# Modem.net
KiCad netlist of a schematic drawn in Altium Designer
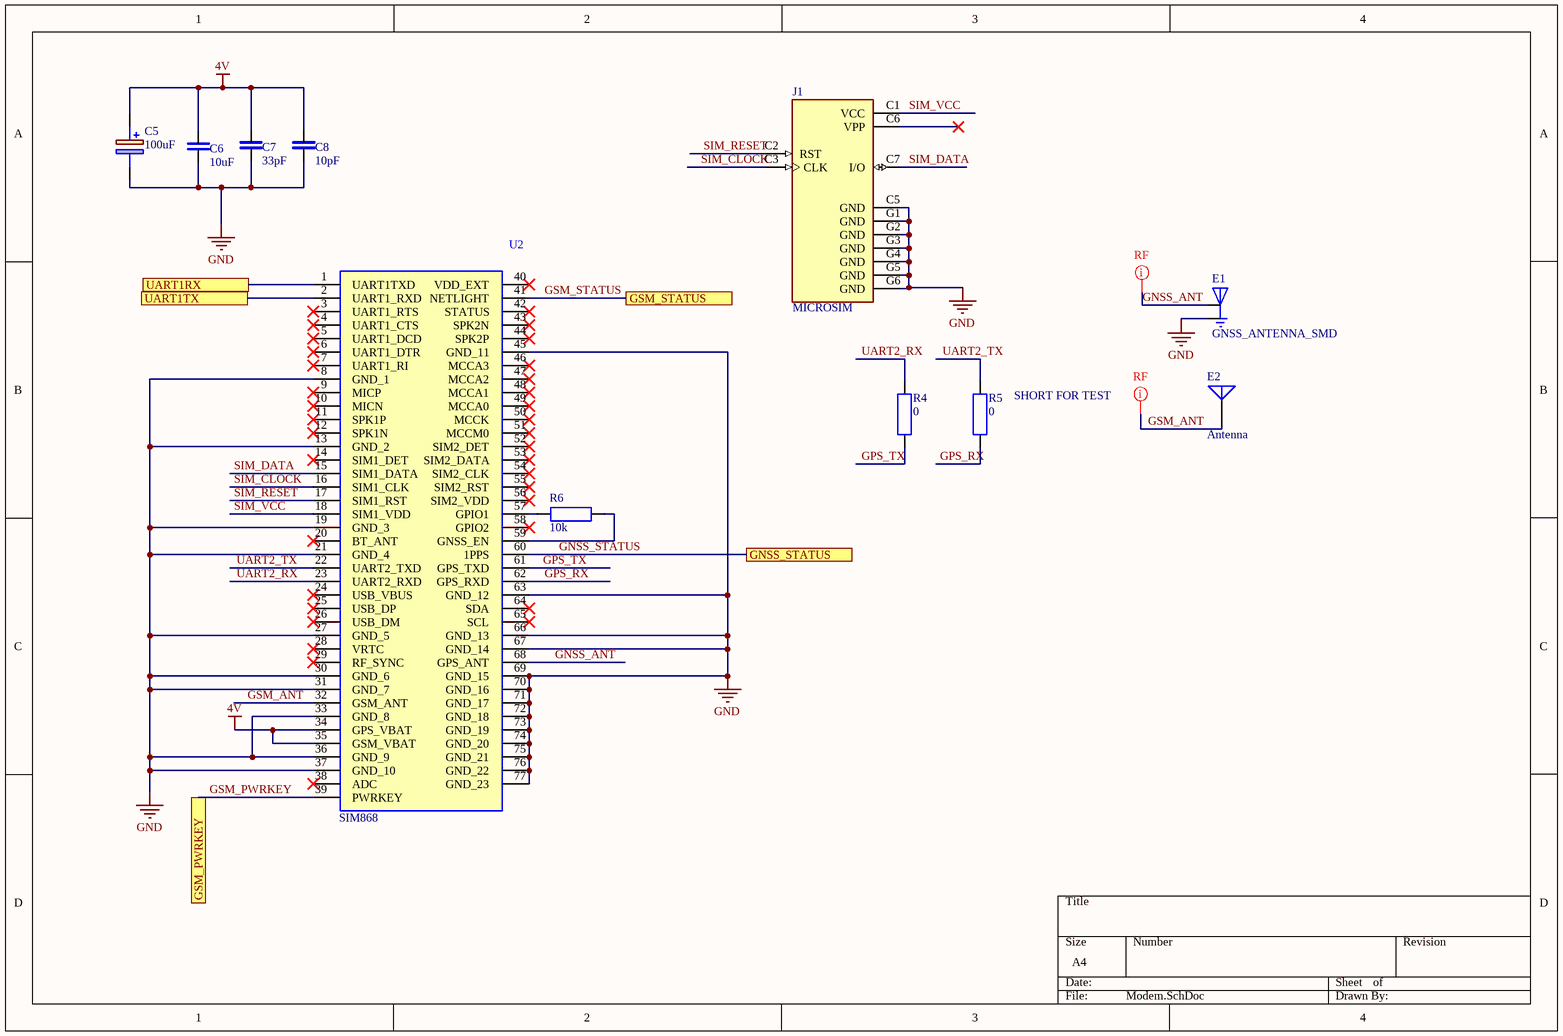
[diagram p0: Modem.SchDoc]

(export (version "E")
  (design (tool "Eeschema 10.0.6"))
  (components
    (comp (ref "C5")
      (value "100uF")
      (footprint "TANTALUM_CAP_0805")
      (description "T491C107K016AT")
      (fields (field (name "MOUSER PART NUMBER") "80-T491C107K016AT"))
      (libsource (lib "Passive_Components") (part "SMT_TANTALUM_CAP"))
    )
    (comp (ref "C6")
      (value "10uF")
      (footprint "CAP_0805")
      (fields (field (name "MP") "LD051A270KAB2A"))
      (libsource (lib "Passive_Components") (part "SMT_CAP"))
    )
    (comp (ref "C7")
      (value "33pF")
      (footprint "CAP_0805")
      (fields (field (name "MP") "LD051A270KAB2A"))
      (libsource (lib "Passive_Components") (part "SMT_CAP"))
    )
    (comp (ref "C8")
      (value "10pF")
      (footprint "CAP_0805")
      (fields (field (name "MP") "LD051A270KAB2A"))
      (libsource (lib "Passive_Components") (part "SMT_CAP"))
    )
    (comp (ref "E1")
      (value "GNSS_ANTENNA_SMD")
      (footprint "GNSS_ANTENNA_SMD")
      (description "Ceramic GNSS antenna 25*25 SMD")
      (fields (field (name "MF") "Linx") (field (name "MP") "ANT-GNSSCP-TH18L1"))
      (libsource (lib "Extras") (part "GNSS_ANTENNA_SMD"))
    )
    (comp (ref "E2")
      (value "Antenna")
      (footprint "PIN1")
      (description "Generic Antenna")
      (fields (field (name "PUBLISHER") "Altium Limited"))
      (libsource (lib "Miscellaneous Devices") (part "Antenna"))
    )
    (comp (ref "J1")
      (value "MICROSIM")
      (footprint "MICROSIM")
      (description "PART NR: 78646-3001")
      (fields (field (name "MP") "78646-3001") (field (name "MF") "Molex"))
      (libsource (lib "Extras") (part "MICROSIM"))
    )
    (comp (ref "R4")
      (value "0")
      (footprint "RES_0805")
      (fields
        (field (name "MP") "2-2176053-0")
        (field (name "TOLERANCE") "1%")
        (field (name "MF") "TE Connectivity")
      )
      (libsource (lib "Passive_Components") (part "SMT_RES"))
    )
    (comp (ref "R5")
      (value "0")
      (footprint "RES_0805")
      (fields
        (field (name "MP") "2-2176053-0")
        (field (name "TOLERANCE") "1%")
        (field (name "MF") "TE Connectivity")
      )
      (libsource (lib "Passive_Components") (part "SMT_RES"))
    )
    (comp (ref "R6")
      (value "10k")
      (footprint "RES_0805")
      (fields
        (field (name "MP") "2-2176053-0")
        (field (name "TOLERANCE") "1%")
        (field (name "MF") "TE Connectivity")
      )
      (libsource (lib "Passive_Components") (part "SMT_RES"))
    )
    (comp (ref "U2")
      (value "GPRS,GSM,GNSS Modem")
      (footprint "SIM868")
      (fields (field (name "MANUFACTURER_PART_NUMBER") "SIM868") (field (name "SYMBOLNAME_1") "SIM868"))
      (libsource (lib "IC") (part "SIM868"))
    )
  )
  (nets
    (net (code "1") (name "/GNSS_ANT") (class "Default")
      (node (ref "E1") (pin "1") (pinfunction "FEEDING_1") (pintype "passive"))
      (node (ref "U2") (pin "68") (pinfunction "GPS_ANT_68") (pintype "power_in"))
    )
    (net (code "2") (name "/GNSS_STATUS") (class "Default")
      (node (ref "U2") (pin "60") (pinfunction "1PPS_60") (pintype "power_in"))
    )
    (net (code "3") (name "/GPS_RX") (class "Default")
      (node (ref "R5") (pin "1") (pinfunction "1_1") (pintype "passive"))
      (node (ref "U2") (pin "62") (pinfunction "GPS_RXD_62") (pintype "power_in"))
    )
    (net (code "4") (name "/GPS_TX") (class "Default")
      (node (ref "R4") (pin "1") (pinfunction "1_1") (pintype "passive"))
      (node (ref "U2") (pin "61") (pinfunction "GPS_TXD_61") (pintype "power_in"))
    )
    (net (code "5") (name "/GSM_ANT") (class "Default")
      (node (ref "E2") (pin "1") (pinfunction "A_1") (pintype "passive"))
      (node (ref "U2") (pin "32") (pinfunction "GSM_ANT_32") (pintype "power_in"))
    )
    (net (code "6") (name "/GSM_PWRKEY") (class "Default")
      (node (ref "U2") (pin "39") (pinfunction "PWRKEY_39") (pintype "power_in"))
    )
    (net (code "7") (name "/GSM_STATUS") (class "Default")
      (node (ref "U2") (pin "41") (pinfunction "NETLIGHT_41") (pintype "power_in"))
    )
    (net (code "8") (name "/SIM_CLOCK") (class "Default")
      (node (ref "J1") (pin "C3") (pinfunction "CLK_C3") (pintype "input"))
      (node (ref "U2") (pin "16") (pinfunction "SIM1_CLK_16") (pintype "power_in"))
    )
    (net (code "9") (name "/SIM_DATA") (class "Default")
      (node (ref "J1") (pin "C7") (pinfunction "I/O_C7") (pintype "bidirectional"))
      (node (ref "U2") (pin "15") (pinfunction "SIM1_DATA_15") (pintype "power_in"))
    )
    (net (code "10") (name "/SIM_RESET") (class "Default")
      (node (ref "J1") (pin "C2") (pinfunction "RST_C2") (pintype "input"))
      (node (ref "U2") (pin "17") (pinfunction "SIM1_RST_17") (pintype "power_in"))
    )
    (net (code "11") (name "/SIM_VCC") (class "Default")
      (node (ref "J1") (pin "C1") (pinfunction "VCC_C1") (pintype "power_in"))
      (node (ref "U2") (pin "18") (pinfunction "SIM1_VDD_18") (pintype "power_in"))
    )
    (net (code "12") (name "/UART1RX") (class "Default")
      (node (ref "U2") (pin "1") (pinfunction "UART1TXD_1") (pintype "power_in"))
    )
    (net (code "13") (name "/UART1TX") (class "Default")
      (node (ref "U2") (pin "2") (pinfunction "UART1_RXD_2") (pintype "power_in"))
    )
    (net (code "14") (name "/UART2_RX") (class "Default")
      (node (ref "R4") (pin "2") (pinfunction "2_2") (pintype "passive"))
      (node (ref "U2") (pin "23") (pinfunction "UART2_RXD_23") (pintype "power_in"))
    )
    (net (code "15") (name "/UART2_TX") (class "Default")
      (node (ref "R5") (pin "2") (pinfunction "2_2") (pintype "passive"))
      (node (ref "U2") (pin "22") (pinfunction "UART2_TXD_22") (pintype "power_in"))
    )
    (net (code "16") (name "4V") (class "Default")
      (node (ref "C5") (pin "1") (pinfunction "+_1") (pintype "passive"))
      (node (ref "C6") (pin "2") (pinfunction "2_2") (pintype "passive"))
      (node (ref "C7") (pin "2") (pinfunction "2_2") (pintype "passive"))
      (node (ref "C8") (pin "2") (pinfunction "2_2") (pintype "passive"))
      (node (ref "U2") (pin "34") (pinfunction "GPS_VBAT_34") (pintype "power_in"))
      (node (ref "U2") (pin "35") (pinfunction "GSM_VBAT_35") (pintype "power_in"))
    )
    (net (code "17") (name "GND") (class "Default")
      (node (ref "C5") (pin "2") (pinfunction "-_2") (pintype "passive"))
      (node (ref "C6") (pin "1") (pinfunction "1_1") (pintype "passive"))
      (node (ref "C7") (pin "1") (pinfunction "1_1") (pintype "passive"))
      (node (ref "C8") (pin "1") (pinfunction "1_1") (pintype "passive"))
      (node (ref "E1") (pin "2") (pinfunction "GND_2") (pintype "power_in"))
      (node (ref "J1") (pin "C5") (pinfunction "GND_C5") (pintype "power_in"))
      (node (ref "J1") (pin "G1") (pinfunction "GND_G1") (pintype "power_in"))
      (node (ref "J1") (pin "G2") (pinfunction "GND_G2") (pintype "power_in"))
      (node (ref "J1") (pin "G3") (pinfunction "GND_G3") (pintype "power_in"))
      (node (ref "J1") (pin "G4") (pinfunction "GND_G4") (pintype "power_in"))
      (node (ref "J1") (pin "G5") (pinfunction "GND_G5") (pintype "power_in"))
      (node (ref "J1") (pin "G6") (pinfunction "GND_G6") (pintype "power_in"))
      (node (ref "U2") (pin "13") (pinfunction "GND_2_13") (pintype "power_in"))
      (node (ref "U2") (pin "19") (pinfunction "GND_3_19") (pintype "power_in"))
      (node (ref "U2") (pin "21") (pinfunction "GND_4_21") (pintype "power_in"))
      (node (ref "U2") (pin "27") (pinfunction "GND_5_27") (pintype "power_in"))
      (node (ref "U2") (pin "30") (pinfunction "GND_6_30") (pintype "power_in"))
      (node (ref "U2") (pin "31") (pinfunction "GND_7_31") (pintype "power_in"))
      (node (ref "U2") (pin "33") (pinfunction "GND_8_33") (pintype "power_in"))
      (node (ref "U2") (pin "36") (pinfunction "GND_9_36") (pintype "power_in"))
      (node (ref "U2") (pin "37") (pinfunction "GND_10_37") (pintype "power_in"))
      (node (ref "U2") (pin "45") (pinfunction "GND_11_45") (pintype "power_in"))
      (node (ref "U2") (pin "63") (pinfunction "GND_12_63") (pintype "power_in"))
      (node (ref "U2") (pin "66") (pinfunction "GND_13_66") (pintype "power_in"))
      (node (ref "U2") (pin "67") (pinfunction "GND_14_67") (pintype "power_in"))
      (node (ref "U2") (pin "69") (pinfunction "GND_15_69") (pintype "power_in"))
      (node (ref "U2") (pin "70") (pinfunction "GND_16_70") (pintype "power_in"))
      (node (ref "U2") (pin "71") (pinfunction "GND_17_71") (pintype "power_in"))
      (node (ref "U2") (pin "72") (pinfunction "GND_18_72") (pintype "power_in"))
      (node (ref "U2") (pin "73") (pinfunction "GND_19_73") (pintype "power_in"))
      (node (ref "U2") (pin "74") (pinfunction "GND_20_74") (pintype "power_in"))
      (node (ref "U2") (pin "75") (pinfunction "GND_21_75") (pintype "power_in"))
      (node (ref "U2") (pin "76") (pinfunction "GND_22_76") (pintype "power_in"))
      (node (ref "U2") (pin "77") (pinfunction "GND_23_77") (pintype "power_in"))
      (node (ref "U2") (pin "8") (pinfunction "GND_1_8") (pintype "power_in"))
    )
    (net (code "18") (name "Net-(U2-GNSS_EN)") (class "Default")
      (node (ref "R6") (pin "2") (pinfunction "2_2") (pintype "passive"))
      (node (ref "U2") (pin "59") (pinfunction "GNSS_EN_59") (pintype "power_in"))
    )
    (net (code "19") (name "Net-(U2-GPIO1)") (class "Default")
      (node (ref "R6") (pin "1") (pinfunction "1_1") (pintype "passive"))
      (node (ref "U2") (pin "57") (pinfunction "GPIO1_57") (pintype "power_in"))
    )
    (net (code "20") (name "unconnected-(J1-VPP-PadC6)") (class "Default")
      (node (ref "J1") (pin "C6") (pinfunction "VPP_C6") (pintype "power_in+no_connect"))
    )
    (net (code "21") (name "unconnected-(U2-ADC-Pad38)") (class "Default")
      (node (ref "U2") (pin "38") (pinfunction "ADC_38") (pintype "power_in+no_connect"))
    )
    (net (code "22") (name "unconnected-(U2-BT_ANT-Pad20)") (class "Default")
      (node (ref "U2") (pin "20") (pinfunction "BT_ANT_20") (pintype "power_in+no_connect"))
    )
    (net (code "23") (name "unconnected-(U2-GPIO2-Pad58)") (class "Default")
      (node (ref "U2") (pin "58") (pinfunction "GPIO2_58") (pintype "power_in+no_connect"))
    )
    (net (code "24") (name "unconnected-(U2-MCCA0-Pad49)") (class "Default")
      (node (ref "U2") (pin "49") (pinfunction "MCCA0_49") (pintype "power_in+no_connect"))
    )
    (net (code "25") (name "unconnected-(U2-MCCA1-Pad48)") (class "Default")
      (node (ref "U2") (pin "48") (pinfunction "MCCA1_48") (pintype "power_in+no_connect"))
    )
    (net (code "26") (name "unconnected-(U2-MCCA2-Pad47)") (class "Default")
      (node (ref "U2") (pin "47") (pinfunction "MCCA2_47") (pintype "power_in+no_connect"))
    )
    (net (code "27") (name "unconnected-(U2-MCCA3-Pad46)") (class "Default")
      (node (ref "U2") (pin "46") (pinfunction "MCCA3_46") (pintype "power_in+no_connect"))
    )
    (net (code "28") (name "unconnected-(U2-MCCK-Pad50)") (class "Default")
      (node (ref "U2") (pin "50") (pinfunction "MCCK_50") (pintype "power_in+no_connect"))
    )
    (net (code "29") (name "unconnected-(U2-MCCM0-Pad51)") (class "Default")
      (node (ref "U2") (pin "51") (pinfunction "MCCM0_51") (pintype "power_in+no_connect"))
    )
    (net (code "30") (name "unconnected-(U2-MICN-Pad10)") (class "Default")
      (node (ref "U2") (pin "10") (pinfunction "MICN_10") (pintype "power_in+no_connect"))
    )
    (net (code "31") (name "unconnected-(U2-MICP-Pad9)") (class "Default")
      (node (ref "U2") (pin "9") (pinfunction "MICP_9") (pintype "power_in+no_connect"))
    )
    (net (code "32") (name "unconnected-(U2-RF_SYNC-Pad29)") (class "Default")
      (node (ref "U2") (pin "29") (pinfunction "RF_SYNC_29") (pintype "power_in+no_connect"))
    )
    (net (code "33") (name "unconnected-(U2-SCL-Pad65)") (class "Default")
      (node (ref "U2") (pin "65") (pinfunction "SCL_65") (pintype "power_in+no_connect"))
    )
    (net (code "34") (name "unconnected-(U2-SDA-Pad64)") (class "Default")
      (node (ref "U2") (pin "64") (pinfunction "SDA_64") (pintype "power_in+no_connect"))
    )
    (net (code "35") (name "unconnected-(U2-SIM1_DET-Pad14)") (class "Default")
      (node (ref "U2") (pin "14") (pinfunction "SIM1_DET_14") (pintype "power_in+no_connect"))
    )
    (net (code "36") (name "unconnected-(U2-SIM2_CLK-Pad54)") (class "Default")
      (node (ref "U2") (pin "54") (pinfunction "SIM2_CLK_54") (pintype "power_in+no_connect"))
    )
    (net (code "37") (name "unconnected-(U2-SIM2_DATA-Pad53)") (class "Default")
      (node (ref "U2") (pin "53") (pinfunction "SIM2_DATA_53") (pintype "power_in+no_connect"))
    )
    (net (code "38") (name "unconnected-(U2-SIM2_DET-Pad52)") (class "Default")
      (node (ref "U2") (pin "52") (pinfunction "SIM2_DET_52") (pintype "power_in+no_connect"))
    )
    (net (code "39") (name "unconnected-(U2-SIM2_RST-Pad55)") (class "Default")
      (node (ref "U2") (pin "55") (pinfunction "SIM2_RST_55") (pintype "power_in+no_connect"))
    )
    (net (code "40") (name "unconnected-(U2-SIM2_VDD-Pad56)") (class "Default")
      (node (ref "U2") (pin "56") (pinfunction "SIM2_VDD_56") (pintype "power_in+no_connect"))
    )
    (net (code "41") (name "unconnected-(U2-SPK1N-Pad12)") (class "Default")
      (node (ref "U2") (pin "12") (pinfunction "SPK1N_12") (pintype "power_in+no_connect"))
    )
    (net (code "42") (name "unconnected-(U2-SPK1P-Pad11)") (class "Default")
      (node (ref "U2") (pin "11") (pinfunction "SPK1P_11") (pintype "power_in+no_connect"))
    )
    (net (code "43") (name "unconnected-(U2-SPK2N-Pad43)") (class "Default")
      (node (ref "U2") (pin "43") (pinfunction "SPK2N_43") (pintype "power_in+no_connect"))
    )
    (net (code "44") (name "unconnected-(U2-SPK2P-Pad44)") (class "Default")
      (node (ref "U2") (pin "44") (pinfunction "SPK2P_44") (pintype "power_in+no_connect"))
    )
    (net (code "45") (name "unconnected-(U2-STATUS-Pad42)") (class "Default")
      (node (ref "U2") (pin "42") (pinfunction "STATUS_42") (pintype "power_in+no_connect"))
    )
    (net (code "46") (name "unconnected-(U2-UART1_CTS-Pad4)") (class "Default")
      (node (ref "U2") (pin "4") (pinfunction "UART1_CTS_4") (pintype "power_in+no_connect"))
    )
    (net (code "47") (name "unconnected-(U2-UART1_DCD-Pad5)") (class "Default")
      (node (ref "U2") (pin "5") (pinfunction "UART1_DCD_5") (pintype "power_in+no_connect"))
    )
    (net (code "48") (name "unconnected-(U2-UART1_DTR-Pad6)") (class "Default")
      (node (ref "U2") (pin "6") (pinfunction "UART1_DTR_6") (pintype "power_in+no_connect"))
    )
    (net (code "49") (name "unconnected-(U2-UART1_RI-Pad7)") (class "Default")
      (node (ref "U2") (pin "7") (pinfunction "UART1_RI_7") (pintype "power_in+no_connect"))
    )
    (net (code "50") (name "unconnected-(U2-UART1_RTS-Pad3)") (class "Default")
      (node (ref "U2") (pin "3") (pinfunction "UART1_RTS_3") (pintype "power_in+no_connect"))
    )
    (net (code "51") (name "unconnected-(U2-USB_DM-Pad26)") (class "Default")
      (node (ref "U2") (pin "26") (pinfunction "USB_DM_26") (pintype "power_in+no_connect"))
    )
    (net (code "52") (name "unconnected-(U2-USB_DP-Pad25)") (class "Default")
      (node (ref "U2") (pin "25") (pinfunction "USB_DP_25") (pintype "power_in+no_connect"))
    )
    (net (code "53") (name "unconnected-(U2-USB_VBUS-Pad24)") (class "Default")
      (node (ref "U2") (pin "24") (pinfunction "USB_VBUS_24") (pintype "power_in+no_connect"))
    )
    (net (code "54") (name "unconnected-(U2-VDD_EXT-Pad40)") (class "Default")
      (node (ref "U2") (pin "40") (pinfunction "VDD_EXT_40") (pintype "power_in+no_connect"))
    )
    (net (code "55") (name "unconnected-(U2-VRTC-Pad28)") (class "Default")
      (node (ref "U2") (pin "28") (pinfunction "VRTC_28") (pintype "power_in+no_connect"))
    )
  )
)
